# untitled.net
KiCad netlist of a schematic drawn in EAGLE
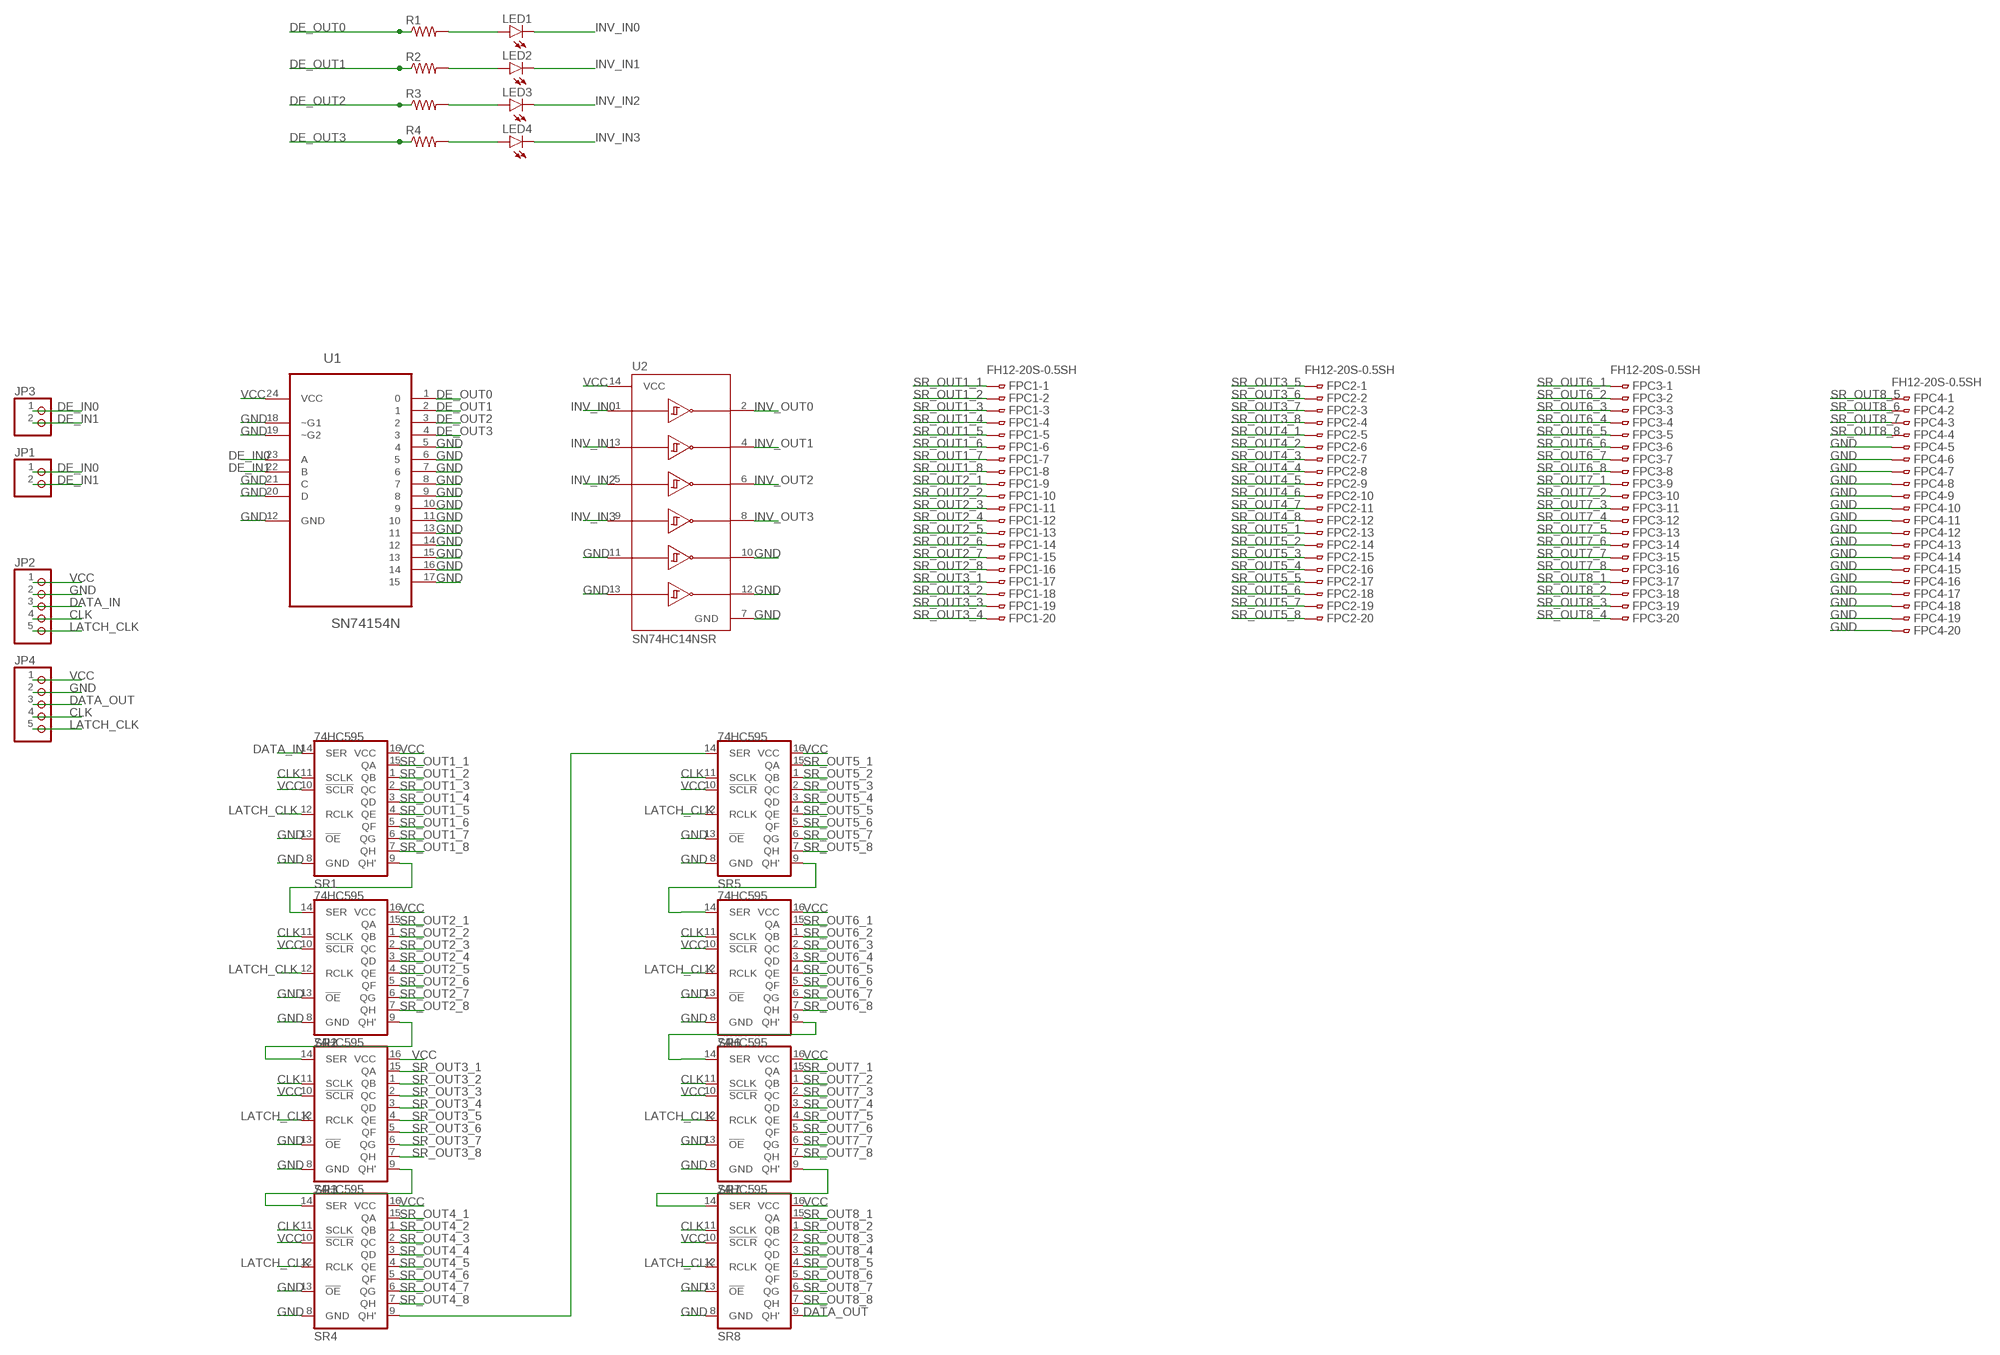
[diagram p0: schematic, sheet 1]

(export (version "E")
  (design (tool "Eeschema 10.0.6"))
  (components
    (comp (ref "FPC1")
      (value "FH12-20S-0.5SH")
      (footprint "eagle-import:FH12-20S-0.5SH")
      (fields (field (name "MPN") "FH12-20S-0.5SH(55)"))
      (libsource (lib "eagle-import") (part "FH12-20S-0.5SH"))
    )
    (comp (ref "FPC2")
      (value "FH12-20S-0.5SH")
      (footprint "eagle-import:FH12-20S-0.5SH")
      (fields (field (name "MPN") "FH12-20S-0.5SH(55)"))
      (libsource (lib "eagle-import") (part "FH12-20S-0.5SH"))
    )
    (comp (ref "FPC3")
      (value "FH12-20S-0.5SH")
      (footprint "eagle-import:FH12-20S-0.5SH")
      (fields (field (name "MPN") "FH12-20S-0.5SH(55)"))
      (libsource (lib "eagle-import") (part "FH12-20S-0.5SH"))
    )
    (comp (ref "FPC4")
      (value "FH12-20S-0.5SH")
      (footprint "eagle-import:FH12-20S-0.5SH")
      (fields (field (name "MPN") "FH12-20S-0.5SH(55)"))
      (libsource (lib "eagle-import") (part "FH12-20S-0.5SH"))
    )
    (comp (ref "JP1")
      (value "PINHD-1X2")
      (footprint "eagle-import:1X02")
      (libsource (lib "eagle-import") (part "PINHD-1X2"))
    )
    (comp (ref "JP2")
      (value "PINHD-1X5")
      (footprint "eagle-import:1X05")
      (libsource (lib "eagle-import") (part "PINHD-1X5"))
    )
    (comp (ref "JP3")
      (value "PINHD-1X2")
      (footprint "eagle-import:1X02")
      (libsource (lib "eagle-import") (part "PINHD-1X2"))
    )
    (comp (ref "JP4")
      (value "PINHD-1X5")
      (footprint "eagle-import:1X05")
      (libsource (lib "eagle-import") (part "PINHD-1X5"))
    )
    (comp (ref "LED1")
      (value "LEDCHIPLED_0805")
      (footprint "eagle-import:CHIPLED_0805")
      (libsource (lib "eagle-import") (part "LEDCHIPLED_0805"))
    )
    (comp (ref "LED2")
      (value "LEDCHIPLED_0805")
      (footprint "eagle-import:CHIPLED_0805")
      (libsource (lib "eagle-import") (part "LEDCHIPLED_0805"))
    )
    (comp (ref "LED3")
      (value "LEDCHIPLED_0805")
      (footprint "eagle-import:CHIPLED_0805")
      (libsource (lib "eagle-import") (part "LEDCHIPLED_0805"))
    )
    (comp (ref "LED4")
      (value "LEDCHIPLED_0805")
      (footprint "eagle-import:CHIPLED_0805")
      (libsource (lib "eagle-import") (part "LEDCHIPLED_0805"))
    )
    (comp (ref "R1")
      (value "R-US_R0805")
      (footprint "eagle-import:R0805")
      (libsource (lib "eagle-import") (part "R-US_R0805"))
    )
    (comp (ref "R2")
      (value "R-US_R0805")
      (footprint "eagle-import:R0805")
      (libsource (lib "eagle-import") (part "R-US_R0805"))
    )
    (comp (ref "R3")
      (value "R-US_R0805")
      (footprint "eagle-import:R0805")
      (libsource (lib "eagle-import") (part "R-US_R0805"))
    )
    (comp (ref "R4")
      (value "R-US_R0805")
      (footprint "eagle-import:R0805")
      (libsource (lib "eagle-import") (part "R-US_R0805"))
    )
    (comp (ref "SR1")
      (value "74HC595")
      (footprint "eagle-import:SO16")
      (fields (field (name "MF") "Nexperia"))
      (libsource (lib "eagle-import") (part "74HC595"))
    )
    (comp (ref "SR2")
      (value "74HC595")
      (footprint "eagle-import:SO16")
      (fields (field (name "MF") "Nexperia"))
      (libsource (lib "eagle-import") (part "74HC595"))
    )
    (comp (ref "SR3")
      (value "74HC595")
      (footprint "eagle-import:SO16")
      (fields (field (name "MF") "Nexperia"))
      (libsource (lib "eagle-import") (part "74HC595"))
    )
    (comp (ref "SR4")
      (value "74HC595")
      (footprint "eagle-import:SO16")
      (fields (field (name "MF") "Nexperia"))
      (libsource (lib "eagle-import") (part "74HC595"))
    )
    (comp (ref "SR5")
      (value "74HC595")
      (footprint "eagle-import:SO16")
      (fields (field (name "MF") "Nexperia"))
      (libsource (lib "eagle-import") (part "74HC595"))
    )
    (comp (ref "SR6")
      (value "74HC595")
      (footprint "eagle-import:SO16")
      (fields (field (name "MF") "Nexperia"))
      (libsource (lib "eagle-import") (part "74HC595"))
    )
    (comp (ref "SR7")
      (value "74HC595")
      (footprint "eagle-import:SO16")
      (fields (field (name "MF") "Nexperia"))
      (libsource (lib "eagle-import") (part "74HC595"))
    )
    (comp (ref "SR8")
      (value "74HC595")
      (footprint "eagle-import:SO16")
      (fields (field (name "MF") "Nexperia"))
      (libsource (lib "eagle-import") (part "74HC595"))
    )
    (comp (ref "U1")
      (value "SN74154N")
      (footprint "eagle-import:DIP254P1080X508-24")
      (fields (field (name "MF") "Texas Instruments"))
      (libsource (lib "eagle-import") (part "SN74154N"))
    )
    (comp (ref "U2")
      (value "SN74HC14NSR")
      (footprint "eagle-import:SOP127P780X200-14N")
      (fields (field (name "MF") "Texas Instruments"))
      (libsource (lib "eagle-import") (part "SN74HC14NSR"))
    )
  )
  (nets
    (net (code "1") (name "/CLK") (class "Default")
      (node (ref "JP2") (pin "4") (pinfunction "4_4") (pintype "passive"))
      (node (ref "JP4") (pin "4") (pinfunction "4_4") (pintype "passive"))
      (node (ref "SR1") (pin "11") (pinfunction "SCLK_11") (pintype "input"))
      (node (ref "SR2") (pin "11") (pinfunction "SCLK_11") (pintype "input"))
      (node (ref "SR3") (pin "11") (pinfunction "SCLK_11") (pintype "input"))
      (node (ref "SR4") (pin "11") (pinfunction "SCLK_11") (pintype "input"))
      (node (ref "SR5") (pin "11") (pinfunction "SCLK_11") (pintype "input"))
      (node (ref "SR6") (pin "11") (pinfunction "SCLK_11") (pintype "input"))
      (node (ref "SR7") (pin "11") (pinfunction "SCLK_11") (pintype "input"))
      (node (ref "SR8") (pin "11") (pinfunction "SCLK_11") (pintype "input"))
    )
    (net (code "2") (name "/DATA_IN") (class "Default")
      (node (ref "JP2") (pin "3") (pinfunction "3_3") (pintype "passive"))
      (node (ref "SR1") (pin "14") (pinfunction "SER_14") (pintype "input"))
    )
    (net (code "3") (name "/DATA_OUT") (class "Default")
      (node (ref "JP4") (pin "3") (pinfunction "3_3") (pintype "passive"))
      (node (ref "SR8") (pin "9") (pinfunction "QH'_9") (pintype "tri_state"))
    )
    (net (code "4") (name "/DE_IN0") (class "Default")
      (node (ref "JP1") (pin "1") (pinfunction "1_1") (pintype "passive"))
      (node (ref "JP3") (pin "1") (pinfunction "1_1") (pintype "passive"))
      (node (ref "U1") (pin "23") (pinfunction "A_23") (pintype "input"))
    )
    (net (code "5") (name "/DE_IN1") (class "Default")
      (node (ref "JP1") (pin "2") (pinfunction "2_2") (pintype "passive"))
      (node (ref "JP3") (pin "2") (pinfunction "2_2") (pintype "passive"))
      (node (ref "U1") (pin "22") (pinfunction "B_22") (pintype "input"))
    )
    (net (code "6") (name "/DE_OUT0") (class "Default")
      (node (ref "R1") (pin "1") (pinfunction "1_1") (pintype "passive"))
      (node (ref "U1") (pin "1") (pinfunction "0_1") (pintype "output"))
    )
    (net (code "7") (name "/DE_OUT1") (class "Default")
      (node (ref "R2") (pin "1") (pinfunction "1_1") (pintype "passive"))
      (node (ref "U1") (pin "2") (pinfunction "1_2") (pintype "output"))
    )
    (net (code "8") (name "/DE_OUT2") (class "Default")
      (node (ref "R3") (pin "1") (pinfunction "1_1") (pintype "passive"))
      (node (ref "U1") (pin "3") (pinfunction "2_3") (pintype "output"))
    )
    (net (code "9") (name "/DE_OUT3") (class "Default")
      (node (ref "R4") (pin "1") (pinfunction "1_1") (pintype "passive"))
      (node (ref "U1") (pin "4") (pinfunction "3_4") (pintype "output"))
    )
    (net (code "10") (name "/GND") (class "Default")
      (node (ref "FPC4") (pin "10") (pinfunction "1_10") (pintype "passive"))
      (node (ref "FPC4") (pin "11") (pinfunction "1_11") (pintype "passive"))
      (node (ref "FPC4") (pin "12") (pinfunction "1_12") (pintype "passive"))
      (node (ref "FPC4") (pin "13") (pinfunction "1_13") (pintype "passive"))
      (node (ref "FPC4") (pin "14") (pinfunction "1_14") (pintype "passive"))
      (node (ref "FPC4") (pin "15") (pinfunction "1_15") (pintype "passive"))
      (node (ref "FPC4") (pin "16") (pinfunction "1_16") (pintype "passive"))
      (node (ref "FPC4") (pin "17") (pinfunction "1_17") (pintype "passive"))
      (node (ref "FPC4") (pin "18") (pinfunction "1_18") (pintype "passive"))
      (node (ref "FPC4") (pin "19") (pinfunction "1_19") (pintype "passive"))
      (node (ref "FPC4") (pin "20") (pinfunction "1_20") (pintype "passive"))
      (node (ref "FPC4") (pin "5") (pinfunction "1_5") (pintype "passive"))
      (node (ref "FPC4") (pin "6") (pinfunction "1_6") (pintype "passive"))
      (node (ref "FPC4") (pin "7") (pinfunction "1_7") (pintype "passive"))
      (node (ref "FPC4") (pin "8") (pinfunction "1_8") (pintype "passive"))
      (node (ref "FPC4") (pin "9") (pinfunction "1_9") (pintype "passive"))
      (node (ref "JP2") (pin "2") (pinfunction "2_2") (pintype "passive"))
      (node (ref "JP4") (pin "2") (pinfunction "2_2") (pintype "passive"))
      (node (ref "SR1") (pin "13") (pinfunction "~{OE}_13") (pintype "input"))
      (node (ref "SR1") (pin "8") (pinfunction "GND_8") (pintype "power_in"))
      (node (ref "SR2") (pin "13") (pinfunction "~{OE}_13") (pintype "input"))
      (node (ref "SR2") (pin "8") (pinfunction "GND_8") (pintype "power_in"))
      (node (ref "SR3") (pin "13") (pinfunction "~{OE}_13") (pintype "input"))
      (node (ref "SR3") (pin "8") (pinfunction "GND_8") (pintype "power_in"))
      (node (ref "SR4") (pin "13") (pinfunction "~{OE}_13") (pintype "input"))
      (node (ref "SR4") (pin "8") (pinfunction "GND_8") (pintype "power_in"))
      (node (ref "SR5") (pin "13") (pinfunction "~{OE}_13") (pintype "input"))
      (node (ref "SR5") (pin "8") (pinfunction "GND_8") (pintype "power_in"))
      (node (ref "SR6") (pin "13") (pinfunction "~{OE}_13") (pintype "input"))
      (node (ref "SR6") (pin "8") (pinfunction "GND_8") (pintype "power_in"))
      (node (ref "SR7") (pin "13") (pinfunction "~{OE}_13") (pintype "input"))
      (node (ref "SR7") (pin "8") (pinfunction "GND_8") (pintype "power_in"))
      (node (ref "SR8") (pin "13") (pinfunction "~{OE}_13") (pintype "input"))
      (node (ref "SR8") (pin "8") (pinfunction "GND_8") (pintype "power_in"))
      (node (ref "U1") (pin "10") (pinfunction "9_10") (pintype "output"))
      (node (ref "U1") (pin "11") (pinfunction "10_11") (pintype "output"))
      (node (ref "U1") (pin "12") (pinfunction "GND_12") (pintype "passive"))
      (node (ref "U1") (pin "13") (pinfunction "11_13") (pintype "output"))
      (node (ref "U1") (pin "14") (pinfunction "12_14") (pintype "output"))
      (node (ref "U1") (pin "15") (pinfunction "13_15") (pintype "output"))
      (node (ref "U1") (pin "16") (pinfunction "14_16") (pintype "output"))
      (node (ref "U1") (pin "17") (pinfunction "15_17") (pintype "output"))
      (node (ref "U1") (pin "18") (pinfunction "~{G1}_18") (pintype "input"))
      (node (ref "U1") (pin "19") (pinfunction "~{G2}_19") (pintype "input"))
      (node (ref "U1") (pin "20") (pinfunction "D_20") (pintype "input"))
      (node (ref "U1") (pin "21") (pinfunction "C_21") (pintype "input"))
      (node (ref "U1") (pin "5") (pinfunction "4_5") (pintype "output"))
      (node (ref "U1") (pin "6") (pinfunction "5_6") (pintype "output"))
      (node (ref "U1") (pin "7") (pinfunction "6_7") (pintype "output"))
      (node (ref "U1") (pin "8") (pinfunction "7_8") (pintype "output"))
      (node (ref "U1") (pin "9") (pinfunction "8_9") (pintype "output"))
      (node (ref "U2") (pin "10") (pinfunction "5Y_10") (pintype "output"))
      (node (ref "U2") (pin "11") (pinfunction "5A_11") (pintype "input"))
      (node (ref "U2") (pin "12") (pinfunction "6Y_12") (pintype "output"))
      (node (ref "U2") (pin "13") (pinfunction "6A_13") (pintype "input"))
      (node (ref "U2") (pin "7") (pinfunction "GND_7") (pintype "power_in"))
    )
    (net (code "11") (name "/INV_IN0") (class "Default")
      (node (ref "LED1") (pin "C") (pinfunction "C_C") (pintype "passive"))
      (node (ref "U2") (pin "1") (pinfunction "1A_1") (pintype "input"))
    )
    (net (code "12") (name "/INV_IN1") (class "Default")
      (node (ref "LED2") (pin "C") (pinfunction "C_C") (pintype "passive"))
      (node (ref "U2") (pin "3") (pinfunction "2A_3") (pintype "input"))
    )
    (net (code "13") (name "/INV_IN2") (class "Default")
      (node (ref "LED3") (pin "C") (pinfunction "C_C") (pintype "passive"))
      (node (ref "U2") (pin "5") (pinfunction "3A_5") (pintype "input"))
    )
    (net (code "14") (name "/INV_IN3") (class "Default")
      (node (ref "LED4") (pin "C") (pinfunction "C_C") (pintype "passive"))
      (node (ref "U2") (pin "9") (pinfunction "4A_9") (pintype "input"))
    )
    (net (code "15") (name "/INV_OUT0") (class "Default")
      (node (ref "U2") (pin "2") (pinfunction "1Y_2") (pintype "output"))
    )
    (net (code "16") (name "/INV_OUT1") (class "Default")
      (node (ref "U2") (pin "4") (pinfunction "2Y_4") (pintype "output"))
    )
    (net (code "17") (name "/INV_OUT2") (class "Default")
      (node (ref "U2") (pin "6") (pinfunction "3Y_6") (pintype "output"))
    )
    (net (code "18") (name "/INV_OUT3") (class "Default")
      (node (ref "U2") (pin "8") (pinfunction "4Y_8") (pintype "output"))
    )
    (net (code "19") (name "/LATCH_CLK") (class "Default")
      (node (ref "JP2") (pin "5") (pinfunction "5_5") (pintype "passive"))
      (node (ref "JP4") (pin "5") (pinfunction "5_5") (pintype "passive"))
      (node (ref "SR1") (pin "12") (pinfunction "RCLK_12") (pintype "input"))
      (node (ref "SR2") (pin "12") (pinfunction "RCLK_12") (pintype "input"))
      (node (ref "SR3") (pin "12") (pinfunction "RCLK_12") (pintype "input"))
      (node (ref "SR4") (pin "12") (pinfunction "RCLK_12") (pintype "input"))
      (node (ref "SR5") (pin "12") (pinfunction "RCLK_12") (pintype "input"))
      (node (ref "SR6") (pin "12") (pinfunction "RCLK_12") (pintype "input"))
      (node (ref "SR7") (pin "12") (pinfunction "RCLK_12") (pintype "input"))
      (node (ref "SR8") (pin "12") (pinfunction "RCLK_12") (pintype "input"))
    )
    (net (code "20") (name "/SR_OUT1_1") (class "Default")
      (node (ref "FPC1") (pin "1") (pinfunction "1_1") (pintype "passive"))
      (node (ref "SR1") (pin "15") (pinfunction "QA_15") (pintype "tri_state"))
    )
    (net (code "21") (name "/SR_OUT1_2") (class "Default")
      (node (ref "FPC1") (pin "2") (pinfunction "1_2") (pintype "passive"))
      (node (ref "SR1") (pin "1") (pinfunction "QB_1") (pintype "tri_state"))
    )
    (net (code "22") (name "/SR_OUT1_3") (class "Default")
      (node (ref "FPC1") (pin "3") (pinfunction "1_3") (pintype "passive"))
      (node (ref "SR1") (pin "2") (pinfunction "QC_2") (pintype "tri_state"))
    )
    (net (code "23") (name "/SR_OUT1_4") (class "Default")
      (node (ref "FPC1") (pin "4") (pinfunction "1_4") (pintype "passive"))
      (node (ref "SR1") (pin "3") (pinfunction "QD_3") (pintype "tri_state"))
    )
    (net (code "24") (name "/SR_OUT1_5") (class "Default")
      (node (ref "FPC1") (pin "5") (pinfunction "1_5") (pintype "passive"))
      (node (ref "SR1") (pin "4") (pinfunction "QE_4") (pintype "tri_state"))
    )
    (net (code "25") (name "/SR_OUT1_6") (class "Default")
      (node (ref "FPC1") (pin "6") (pinfunction "1_6") (pintype "passive"))
      (node (ref "SR1") (pin "5") (pinfunction "QF_5") (pintype "tri_state"))
    )
    (net (code "26") (name "/SR_OUT1_7") (class "Default")
      (node (ref "FPC1") (pin "7") (pinfunction "1_7") (pintype "passive"))
      (node (ref "SR1") (pin "6") (pinfunction "QG_6") (pintype "tri_state"))
    )
    (net (code "27") (name "/SR_OUT1_8") (class "Default")
      (node (ref "FPC1") (pin "8") (pinfunction "1_8") (pintype "passive"))
      (node (ref "SR1") (pin "7") (pinfunction "QH_7") (pintype "tri_state"))
    )
    (net (code "28") (name "/SR_OUT2_1") (class "Default")
      (node (ref "FPC1") (pin "9") (pinfunction "1_9") (pintype "passive"))
      (node (ref "SR2") (pin "15") (pinfunction "QA_15") (pintype "tri_state"))
    )
    (net (code "29") (name "/SR_OUT2_2") (class "Default")
      (node (ref "FPC1") (pin "10") (pinfunction "1_10") (pintype "passive"))
      (node (ref "SR2") (pin "1") (pinfunction "QB_1") (pintype "tri_state"))
    )
    (net (code "30") (name "/SR_OUT2_3") (class "Default")
      (node (ref "FPC1") (pin "11") (pinfunction "1_11") (pintype "passive"))
      (node (ref "SR2") (pin "2") (pinfunction "QC_2") (pintype "tri_state"))
    )
    (net (code "31") (name "/SR_OUT2_4") (class "Default")
      (node (ref "FPC1") (pin "12") (pinfunction "1_12") (pintype "passive"))
      (node (ref "SR2") (pin "3") (pinfunction "QD_3") (pintype "tri_state"))
    )
    (net (code "32") (name "/SR_OUT2_5") (class "Default")
      (node (ref "FPC1") (pin "13") (pinfunction "1_13") (pintype "passive"))
      (node (ref "SR2") (pin "4") (pinfunction "QE_4") (pintype "tri_state"))
    )
    (net (code "33") (name "/SR_OUT2_6") (class "Default")
      (node (ref "FPC1") (pin "14") (pinfunction "1_14") (pintype "passive"))
      (node (ref "SR2") (pin "5") (pinfunction "QF_5") (pintype "tri_state"))
    )
    (net (code "34") (name "/SR_OUT2_7") (class "Default")
      (node (ref "FPC1") (pin "15") (pinfunction "1_15") (pintype "passive"))
      (node (ref "SR2") (pin "6") (pinfunction "QG_6") (pintype "tri_state"))
    )
    (net (code "35") (name "/SR_OUT2_8") (class "Default")
      (node (ref "FPC1") (pin "16") (pinfunction "1_16") (pintype "passive"))
      (node (ref "SR2") (pin "7") (pinfunction "QH_7") (pintype "tri_state"))
    )
    (net (code "36") (name "/SR_OUT3_1") (class "Default")
      (node (ref "FPC1") (pin "17") (pinfunction "1_17") (pintype "passive"))
      (node (ref "SR3") (pin "15") (pinfunction "QA_15") (pintype "tri_state"))
    )
    (net (code "37") (name "/SR_OUT3_2") (class "Default")
      (node (ref "FPC1") (pin "18") (pinfunction "1_18") (pintype "passive"))
      (node (ref "SR3") (pin "1") (pinfunction "QB_1") (pintype "tri_state"))
    )
    (net (code "38") (name "/SR_OUT3_3") (class "Default")
      (node (ref "FPC1") (pin "19") (pinfunction "1_19") (pintype "passive"))
      (node (ref "SR3") (pin "2") (pinfunction "QC_2") (pintype "tri_state"))
    )
    (net (code "39") (name "/SR_OUT3_4") (class "Default")
      (node (ref "FPC1") (pin "20") (pinfunction "1_20") (pintype "passive"))
      (node (ref "SR3") (pin "3") (pinfunction "QD_3") (pintype "tri_state"))
    )
    (net (code "40") (name "/SR_OUT3_5") (class "Default")
      (node (ref "FPC2") (pin "1") (pinfunction "1_1") (pintype "passive"))
      (node (ref "SR3") (pin "4") (pinfunction "QE_4") (pintype "tri_state"))
    )
    (net (code "41") (name "/SR_OUT3_6") (class "Default")
      (node (ref "FPC2") (pin "2") (pinfunction "1_2") (pintype "passive"))
      (node (ref "SR3") (pin "5") (pinfunction "QF_5") (pintype "tri_state"))
    )
    (net (code "42") (name "/SR_OUT3_7") (class "Default")
      (node (ref "FPC2") (pin "3") (pinfunction "1_3") (pintype "passive"))
      (node (ref "SR3") (pin "6") (pinfunction "QG_6") (pintype "tri_state"))
    )
    (net (code "43") (name "/SR_OUT3_8") (class "Default")
      (node (ref "FPC2") (pin "4") (pinfunction "1_4") (pintype "passive"))
      (node (ref "SR3") (pin "7") (pinfunction "QH_7") (pintype "tri_state"))
    )
    (net (code "44") (name "/SR_OUT4_1") (class "Default")
      (node (ref "FPC2") (pin "5") (pinfunction "1_5") (pintype "passive"))
      (node (ref "SR4") (pin "15") (pinfunction "QA_15") (pintype "tri_state"))
    )
    (net (code "45") (name "/SR_OUT4_2") (class "Default")
      (node (ref "FPC2") (pin "6") (pinfunction "1_6") (pintype "passive"))
      (node (ref "SR4") (pin "1") (pinfunction "QB_1") (pintype "tri_state"))
    )
    (net (code "46") (name "/SR_OUT4_3") (class "Default")
      (node (ref "FPC2") (pin "7") (pinfunction "1_7") (pintype "passive"))
      (node (ref "SR4") (pin "2") (pinfunction "QC_2") (pintype "tri_state"))
    )
    (net (code "47") (name "/SR_OUT4_4") (class "Default")
      (node (ref "FPC2") (pin "8") (pinfunction "1_8") (pintype "passive"))
      (node (ref "SR4") (pin "3") (pinfunction "QD_3") (pintype "tri_state"))
    )
    (net (code "48") (name "/SR_OUT4_5") (class "Default")
      (node (ref "FPC2") (pin "9") (pinfunction "1_9") (pintype "passive"))
      (node (ref "SR4") (pin "4") (pinfunction "QE_4") (pintype "tri_state"))
    )
    (net (code "49") (name "/SR_OUT4_6") (class "Default")
      (node (ref "FPC2") (pin "10") (pinfunction "1_10") (pintype "passive"))
      (node (ref "SR4") (pin "5") (pinfunction "QF_5") (pintype "tri_state"))
    )
    (net (code "50") (name "/SR_OUT4_7") (class "Default")
      (node (ref "FPC2") (pin "11") (pinfunction "1_11") (pintype "passive"))
      (node (ref "SR4") (pin "6") (pinfunction "QG_6") (pintype "tri_state"))
    )
    (net (code "51") (name "/SR_OUT4_8") (class "Default")
      (node (ref "FPC2") (pin "12") (pinfunction "1_12") (pintype "passive"))
      (node (ref "SR4") (pin "7") (pinfunction "QH_7") (pintype "tri_state"))
    )
    (net (code "52") (name "/SR_OUT5_1") (class "Default")
      (node (ref "FPC2") (pin "13") (pinfunction "1_13") (pintype "passive"))
      (node (ref "SR5") (pin "15") (pinfunction "QA_15") (pintype "tri_state"))
    )
    (net (code "53") (name "/SR_OUT5_2") (class "Default")
      (node (ref "FPC2") (pin "14") (pinfunction "1_14") (pintype "passive"))
      (node (ref "SR5") (pin "1") (pinfunction "QB_1") (pintype "tri_state"))
    )
    (net (code "54") (name "/SR_OUT5_3") (class "Default")
      (node (ref "FPC2") (pin "15") (pinfunction "1_15") (pintype "passive"))
      (node (ref "SR5") (pin "2") (pinfunction "QC_2") (pintype "tri_state"))
    )
    (net (code "55") (name "/SR_OUT5_4") (class "Default")
      (node (ref "FPC2") (pin "16") (pinfunction "1_16") (pintype "passive"))
      (node (ref "SR5") (pin "3") (pinfunction "QD_3") (pintype "tri_state"))
    )
    (net (code "56") (name "/SR_OUT5_5") (class "Default")
      (node (ref "FPC2") (pin "17") (pinfunction "1_17") (pintype "passive"))
      (node (ref "SR5") (pin "4") (pinfunction "QE_4") (pintype "tri_state"))
    )
    (net (code "57") (name "/SR_OUT5_6") (class "Default")
      (node (ref "FPC2") (pin "18") (pinfunction "1_18") (pintype "passive"))
      (node (ref "SR5") (pin "5") (pinfunction "QF_5") (pintype "tri_state"))
    )
    (net (code "58") (name "/SR_OUT5_7") (class "Default")
      (node (ref "FPC2") (pin "19") (pinfunction "1_19") (pintype "passive"))
      (node (ref "SR5") (pin "6") (pinfunction "QG_6") (pintype "tri_state"))
    )
    (net (code "59") (name "/SR_OUT5_8") (class "Default")
      (node (ref "FPC2") (pin "20") (pinfunction "1_20") (pintype "passive"))
      (node (ref "SR5") (pin "7") (pinfunction "QH_7") (pintype "tri_state"))
    )
    (net (code "60") (name "/SR_OUT6_1") (class "Default")
      (node (ref "FPC3") (pin "1") (pinfunction "1_1") (pintype "passive"))
      (node (ref "SR6") (pin "15") (pinfunction "QA_15") (pintype "tri_state"))
    )
    (net (code "61") (name "/SR_OUT6_2") (class "Default")
      (node (ref "FPC3") (pin "2") (pinfunction "1_2") (pintype "passive"))
      (node (ref "SR6") (pin "1") (pinfunction "QB_1") (pintype "tri_state"))
    )
    (net (code "62") (name "/SR_OUT6_3") (class "Default")
      (node (ref "FPC3") (pin "3") (pinfunction "1_3") (pintype "passive"))
      (node (ref "SR6") (pin "2") (pinfunction "QC_2") (pintype "tri_state"))
    )
    (net (code "63") (name "/SR_OUT6_4") (class "Default")
      (node (ref "FPC3") (pin "4") (pinfunction "1_4") (pintype "passive"))
      (node (ref "SR6") (pin "3") (pinfunction "QD_3") (pintype "tri_state"))
    )
    (net (code "64") (name "/SR_OUT6_5") (class "Default")
      (node (ref "FPC3") (pin "5") (pinfunction "1_5") (pintype "passive"))
      (node (ref "SR6") (pin "4") (pinfunction "QE_4") (pintype "tri_state"))
    )
    (net (code "65") (name "/SR_OUT6_6") (class "Default")
      (node (ref "FPC3") (pin "6") (pinfunction "1_6") (pintype "passive"))
      (node (ref "SR6") (pin "5") (pinfunction "QF_5") (pintype "tri_state"))
    )
    (net (code "66") (name "/SR_OUT6_7") (class "Default")
      (node (ref "FPC3") (pin "7") (pinfunction "1_7") (pintype "passive"))
      (node (ref "SR6") (pin "6") (pinfunction "QG_6") (pintype "tri_state"))
    )
    (net (code "67") (name "/SR_OUT6_8") (class "Default")
      (node (ref "FPC3") (pin "8") (pinfunction "1_8") (pintype "passive"))
      (node (ref "SR6") (pin "7") (pinfunction "QH_7") (pintype "tri_state"))
    )
    (net (code "68") (name "/SR_OUT7_1") (class "Default")
      (node (ref "FPC3") (pin "9") (pinfunction "1_9") (pintype "passive"))
      (node (ref "SR7") (pin "15") (pinfunction "QA_15") (pintype "tri_state"))
    )
    (net (code "69") (name "/SR_OUT7_2") (class "Default")
      (node (ref "FPC3") (pin "10") (pinfunction "1_10") (pintype "passive"))
      (node (ref "SR7") (pin "1") (pinfunction "QB_1") (pintype "tri_state"))
    )
    (net (code "70") (name "/SR_OUT7_3") (class "Default")
      (node (ref "FPC3") (pin "11") (pinfunction "1_11") (pintype "passive"))
      (node (ref "SR7") (pin "2") (pinfunction "QC_2") (pintype "tri_state"))
    )
    (net (code "71") (name "/SR_OUT7_4") (class "Default")
      (node (ref "FPC3") (pin "12") (pinfunction "1_12") (pintype "passive"))
      (node (ref "SR7") (pin "3") (pinfunction "QD_3") (pintype "tri_state"))
    )
    (net (code "72") (name "/SR_OUT7_5") (class "Default")
      (node (ref "FPC3") (pin "13") (pinfunction "1_13") (pintype "passive"))
      (node (ref "SR7") (pin "4") (pinfunction "QE_4") (pintype "tri_state"))
    )
    (net (code "73") (name "/SR_OUT7_6") (class "Default")
      (node (ref "FPC3") (pin "14") (pinfunction "1_14") (pintype "passive"))
      (node (ref "SR7") (pin "5") (pinfunction "QF_5") (pintype "tri_state"))
    )
    (net (code "74") (name "/SR_OUT7_7") (class "Default")
      (node (ref "FPC3") (pin "15") (pinfunction "1_15") (pintype "passive"))
      (node (ref "SR7") (pin "6") (pinfunction "QG_6") (pintype "tri_state"))
    )
    (net (code "75") (name "/SR_OUT7_8") (class "Default")
      (node (ref "FPC3") (pin "16") (pinfunction "1_16") (pintype "passive"))
      (node (ref "SR7") (pin "7") (pinfunction "QH_7") (pintype "tri_state"))
    )
    (net (code "76") (name "/SR_OUT8_1") (class "Default")
      (node (ref "FPC3") (pin "17") (pinfunction "1_17") (pintype "passive"))
      (node (ref "SR8") (pin "15") (pinfunction "QA_15") (pintype "tri_state"))
    )
    (net (code "77") (name "/SR_OUT8_2") (class "Default")
      (node (ref "FPC3") (pin "18") (pinfunction "1_18") (pintype "passive"))
      (node (ref "SR8") (pin "1") (pinfunction "QB_1") (pintype "tri_state"))
    )
    (net (code "78") (name "/SR_OUT8_3") (class "Default")
      (node (ref "FPC3") (pin "19") (pinfunction "1_19") (pintype "passive"))
      (node (ref "SR8") (pin "2") (pinfunction "QC_2") (pintype "tri_state"))
    )
    (net (code "79") (name "/SR_OUT8_4") (class "Default")
      (node (ref "FPC3") (pin "20") (pinfunction "1_20") (pintype "passive"))
      (node (ref "SR8") (pin "3") (pinfunction "QD_3") (pintype "tri_state"))
    )
    (net (code "80") (name "/SR_OUT8_5") (class "Default")
      (node (ref "FPC4") (pin "1") (pinfunction "1_1") (pintype "passive"))
      (node (ref "SR8") (pin "4") (pinfunction "QE_4") (pintype "tri_state"))
    )
    (net (code "81") (name "/SR_OUT8_6") (class "Default")
      (node (ref "FPC4") (pin "2") (pinfunction "1_2") (pintype "passive"))
      (node (ref "SR8") (pin "5") (pinfunction "QF_5") (pintype "tri_state"))
    )
    (net (code "82") (name "/SR_OUT8_7") (class "Default")
      (node (ref "FPC4") (pin "3") (pinfunction "1_3") (pintype "passive"))
      (node (ref "SR8") (pin "6") (pinfunction "QG_6") (pintype "tri_state"))
    )
    (net (code "83") (name "/SR_OUT8_8") (class "Default")
      (node (ref "FPC4") (pin "4") (pinfunction "1_4") (pintype "passive"))
      (node (ref "SR8") (pin "7") (pinfunction "QH_7") (pintype "tri_state"))
    )
    (net (code "84") (name "/VCC") (class "Default")
      (node (ref "JP2") (pin "1") (pinfunction "1_1") (pintype "passive"))
      (node (ref "JP4") (pin "1") (pinfunction "1_1") (pintype "passive"))
      (node (ref "SR1") (pin "10") (pinfunction "~{SCLR}_10") (pintype "input"))
      (node (ref "SR1") (pin "16") (pinfunction "VCC_16") (pintype "power_in"))
      (node (ref "SR2") (pin "10") (pinfunction "~{SCLR}_10") (pintype "input"))
      (node (ref "SR2") (pin "16") (pinfunction "VCC_16") (pintype "power_in"))
      (node (ref "SR3") (pin "10") (pinfunction "~{SCLR}_10") (pintype "input"))
      (node (ref "SR3") (pin "16") (pinfunction "VCC_16") (pintype "power_in"))
      (node (ref "SR4") (pin "10") (pinfunction "~{SCLR}_10") (pintype "input"))
      (node (ref "SR4") (pin "16") (pinfunction "VCC_16") (pintype "power_in"))
      (node (ref "SR5") (pin "10") (pinfunction "~{SCLR}_10") (pintype "input"))
      (node (ref "SR5") (pin "16") (pinfunction "VCC_16") (pintype "power_in"))
      (node (ref "SR6") (pin "10") (pinfunction "~{SCLR}_10") (pintype "input"))
      (node (ref "SR6") (pin "16") (pinfunction "VCC_16") (pintype "power_in"))
      (node (ref "SR7") (pin "10") (pinfunction "~{SCLR}_10") (pintype "input"))
      (node (ref "SR7") (pin "16") (pinfunction "VCC_16") (pintype "power_in"))
      (node (ref "SR8") (pin "10") (pinfunction "~{SCLR}_10") (pintype "input"))
      (node (ref "SR8") (pin "16") (pinfunction "VCC_16") (pintype "power_in"))
      (node (ref "U1") (pin "24") (pinfunction "VCC_24") (pintype "power_in"))
      (node (ref "U2") (pin "14") (pinfunction "VCC_14") (pintype "power_in"))
    )
    (net (code "85") (name "Net-(LED1-PadA)") (class "Default")
      (node (ref "LED1") (pin "A") (pinfunction "A_A") (pintype "passive"))
      (node (ref "R1") (pin "2") (pinfunction "2_2") (pintype "passive"))
    )
    (net (code "86") (name "Net-(LED2-PadA)") (class "Default")
      (node (ref "LED2") (pin "A") (pinfunction "A_A") (pintype "passive"))
      (node (ref "R2") (pin "2") (pinfunction "2_2") (pintype "passive"))
    )
    (net (code "87") (name "Net-(LED3-PadA)") (class "Default")
      (node (ref "LED3") (pin "A") (pinfunction "A_A") (pintype "passive"))
      (node (ref "R3") (pin "2") (pinfunction "2_2") (pintype "passive"))
    )
    (net (code "88") (name "Net-(LED4-PadA)") (class "Default")
      (node (ref "LED4") (pin "A") (pinfunction "A_A") (pintype "passive"))
      (node (ref "R4") (pin "2") (pinfunction "2_2") (pintype "passive"))
    )
    (net (code "89") (name "Net-(SR1-QH')") (class "Default")
      (node (ref "SR1") (pin "9") (pinfunction "QH'_9") (pintype "tri_state"))
      (node (ref "SR2") (pin "14") (pinfunction "SER_14") (pintype "input"))
    )
    (net (code "90") (name "Net-(SR2-QH')") (class "Default")
      (node (ref "SR2") (pin "9") (pinfunction "QH'_9") (pintype "tri_state"))
      (node (ref "SR3") (pin "14") (pinfunction "SER_14") (pintype "input"))
    )
    (net (code "91") (name "Net-(SR3-QH')") (class "Default")
      (node (ref "SR3") (pin "9") (pinfunction "QH'_9") (pintype "tri_state"))
      (node (ref "SR4") (pin "14") (pinfunction "SER_14") (pintype "input"))
    )
    (net (code "92") (name "Net-(SR4-QH')") (class "Default")
      (node (ref "SR4") (pin "9") (pinfunction "QH'_9") (pintype "tri_state"))
      (node (ref "SR5") (pin "14") (pinfunction "SER_14") (pintype "input"))
    )
    (net (code "93") (name "Net-(SR5-QH')") (class "Default")
      (node (ref "SR5") (pin "9") (pinfunction "QH'_9") (pintype "tri_state"))
      (node (ref "SR6") (pin "14") (pinfunction "SER_14") (pintype "input"))
    )
    (net (code "94") (name "Net-(SR6-QH')") (class "Default")
      (node (ref "SR6") (pin "9") (pinfunction "QH'_9") (pintype "tri_state"))
      (node (ref "SR7") (pin "14") (pinfunction "SER_14") (pintype "input"))
    )
    (net (code "95") (name "Net-(SR7-QH')") (class "Default")
      (node (ref "SR7") (pin "9") (pinfunction "QH'_9") (pintype "tri_state"))
      (node (ref "SR8") (pin "14") (pinfunction "SER_14") (pintype "input"))
    )
  )
)
